# avt-trigger-shield.net
KiCad netlist of a schematic drawn in EAGLE
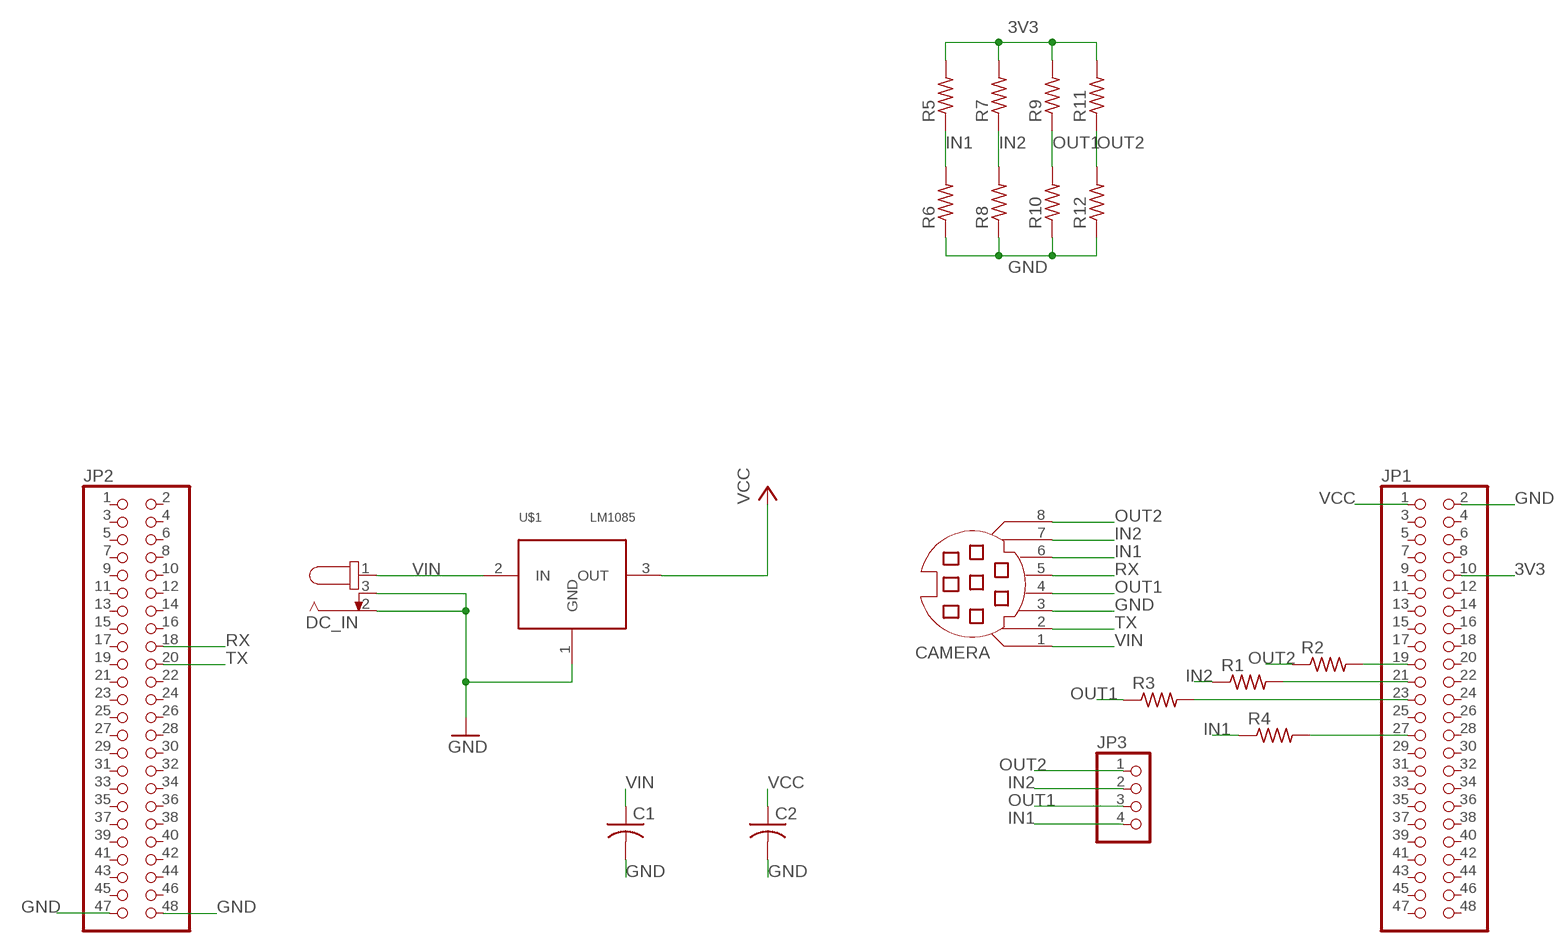
[diagram p0: schematic, sheet 1]

(export (version "E")
  (design (tool "Eeschema 10.0.6"))
  (components
    (comp (ref "C1")
      (value "C-USC1206")
      (footprint "eagle-import:C1206")
      (libsource (lib "eagle-import") (part "C-USC1206"))
    )
    (comp (ref "C2")
      (value "C-USC1206")
      (footprint "eagle-import:C1206")
      (libsource (lib "eagle-import") (part "C-USC1206"))
    )
    (comp (ref "CAMERA")
      (value "MD08SS")
      (footprint "eagle-import:MDIN08SS")
      (libsource (lib "eagle-import") (part "MD08SS"))
    )
    (comp (ref "DC_IN")
      (value "694106105102")
      (footprint "eagle-import:694106105102")
      (libsource (lib "eagle-import") (part "694106105102"))
    )
    (comp (ref "JP1")
      (value "PINHD-2X24")
      (footprint "eagle-import:2X24")
      (libsource (lib "eagle-import") (part "PINHD-2X24"))
    )
    (comp (ref "JP2")
      (value "PINHD-2X24")
      (footprint "eagle-import:2X24")
      (libsource (lib "eagle-import") (part "PINHD-2X24"))
    )
    (comp (ref "JP3")
      (value "PINHD-1X4")
      (footprint "eagle-import:1X04")
      (libsource (lib "eagle-import") (part "PINHD-1X4"))
    )
    (comp (ref "R1")
      (value "R-US_R0603")
      (footprint "eagle-import:R0603")
      (libsource (lib "eagle-import") (part "R-US_R0603"))
    )
    (comp (ref "R2")
      (value "R-US_R0603")
      (footprint "eagle-import:R0603")
      (libsource (lib "eagle-import") (part "R-US_R0603"))
    )
    (comp (ref "R3")
      (value "R-US_R0603")
      (footprint "eagle-import:R0603")
      (libsource (lib "eagle-import") (part "R-US_R0603"))
    )
    (comp (ref "R4")
      (value "R-US_R0603")
      (footprint "eagle-import:R0603")
      (libsource (lib "eagle-import") (part "R-US_R0603"))
    )
    (comp (ref "R5")
      (value "R-US_R0603")
      (footprint "eagle-import:R0603")
      (libsource (lib "eagle-import") (part "R-US_R0603"))
    )
    (comp (ref "R6")
      (value "R-US_R0603")
      (footprint "eagle-import:R0603")
      (libsource (lib "eagle-import") (part "R-US_R0603"))
    )
    (comp (ref "R7")
      (value "R-US_R0603")
      (footprint "eagle-import:R0603")
      (libsource (lib "eagle-import") (part "R-US_R0603"))
    )
    (comp (ref "R8")
      (value "R-US_R0603")
      (footprint "eagle-import:R0603")
      (libsource (lib "eagle-import") (part "R-US_R0603"))
    )
    (comp (ref "R9")
      (value "R-US_R0603")
      (footprint "eagle-import:R0603")
      (libsource (lib "eagle-import") (part "R-US_R0603"))
    )
    (comp (ref "R10")
      (value "R-US_R0603")
      (footprint "eagle-import:R0603")
      (libsource (lib "eagle-import") (part "R-US_R0603"))
    )
    (comp (ref "R11")
      (value "R-US_R0603")
      (footprint "eagle-import:R0603")
      (libsource (lib "eagle-import") (part "R-US_R0603"))
    )
    (comp (ref "R12")
      (value "R-US_R0603")
      (footprint "eagle-import:R0603")
      (libsource (lib "eagle-import") (part "R-US_R0603"))
    )
    (comp (ref "U$1")
      (value "LM1085")
      (footprint "eagle-import:TO263")
      (libsource (lib "eagle-import") (part "LM1085"))
    )
  )
  (nets
    (net (code "1") (name "/3V3") (class "Default")
      (node (ref "JP1") (pin "10") (pinfunction "10_10") (pintype "passive"))
      (node (ref "R11") (pin "2") (pinfunction "2_2") (pintype "passive"))
      (node (ref "R5") (pin "2") (pinfunction "2_2") (pintype "passive"))
      (node (ref "R7") (pin "2") (pinfunction "2_2") (pintype "passive"))
      (node (ref "R9") (pin "2") (pinfunction "2_2") (pintype "passive"))
    )
    (net (code "2") (name "/IN1") (class "Default")
      (node (ref "CAMERA") (pin "6") (pinfunction "6_6") (pintype "passive"))
      (node (ref "JP3") (pin "4") (pinfunction "4_4") (pintype "passive"))
      (node (ref "R4") (pin "1") (pinfunction "1_1") (pintype "passive"))
      (node (ref "R5") (pin "1") (pinfunction "1_1") (pintype "passive"))
      (node (ref "R6") (pin "2") (pinfunction "2_2") (pintype "passive"))
    )
    (net (code "3") (name "/IN2") (class "Default")
      (node (ref "CAMERA") (pin "7") (pinfunction "7_7") (pintype "passive"))
      (node (ref "JP3") (pin "2") (pinfunction "2_2") (pintype "passive"))
      (node (ref "R1") (pin "1") (pinfunction "1_1") (pintype "passive"))
      (node (ref "R7") (pin "1") (pinfunction "1_1") (pintype "passive"))
      (node (ref "R8") (pin "2") (pinfunction "2_2") (pintype "passive"))
    )
    (net (code "4") (name "/OUT1") (class "Default")
      (node (ref "CAMERA") (pin "4") (pinfunction "4_4") (pintype "passive"))
      (node (ref "JP3") (pin "3") (pinfunction "3_3") (pintype "passive"))
      (node (ref "R10") (pin "2") (pinfunction "2_2") (pintype "passive"))
      (node (ref "R3") (pin "1") (pinfunction "1_1") (pintype "passive"))
      (node (ref "R9") (pin "1") (pinfunction "1_1") (pintype "passive"))
    )
    (net (code "5") (name "/OUT2") (class "Default")
      (node (ref "CAMERA") (pin "8") (pinfunction "8_8") (pintype "passive"))
      (node (ref "JP3") (pin "1") (pinfunction "1_1") (pintype "passive"))
      (node (ref "R11") (pin "1") (pinfunction "1_1") (pintype "passive"))
      (node (ref "R12") (pin "2") (pinfunction "2_2") (pintype "passive"))
      (node (ref "R2") (pin "1") (pinfunction "1_1") (pintype "passive"))
    )
    (net (code "6") (name "/RX") (class "Default")
      (node (ref "CAMERA") (pin "5") (pinfunction "5_5") (pintype "passive"))
      (node (ref "JP2") (pin "18") (pinfunction "18_18") (pintype "passive"))
    )
    (net (code "7") (name "/TX") (class "Default")
      (node (ref "CAMERA") (pin "2") (pinfunction "2_2") (pintype "passive"))
      (node (ref "JP2") (pin "20") (pinfunction "20_20") (pintype "passive"))
    )
    (net (code "8") (name "/VIN") (class "Default")
      (node (ref "C1") (pin "1") (pinfunction "1_1") (pintype "passive"))
      (node (ref "CAMERA") (pin "1") (pinfunction "1_1") (pintype "passive"))
      (node (ref "DC_IN") (pin "1") (pinfunction "1_1") (pintype "passive"))
      (node (ref "U$1") (pin "2") (pinfunction "IN_2") (pintype "bidirectional"))
    )
    (net (code "9") (name "GND") (class "Default")
      (node (ref "C1") (pin "2") (pinfunction "2_2") (pintype "passive"))
      (node (ref "C2") (pin "2") (pinfunction "2_2") (pintype "passive"))
      (node (ref "CAMERA") (pin "3") (pinfunction "3_3") (pintype "passive"))
      (node (ref "DC_IN") (pin "2") (pinfunction "2_2") (pintype "passive"))
      (node (ref "DC_IN") (pin "3") (pinfunction "3_3") (pintype "passive"))
      (node (ref "JP1") (pin "2") (pinfunction "2_2") (pintype "passive"))
      (node (ref "JP2") (pin "47") (pinfunction "47_47") (pintype "passive"))
      (node (ref "JP2") (pin "48") (pinfunction "48_48") (pintype "passive"))
      (node (ref "R10") (pin "1") (pinfunction "1_1") (pintype "passive"))
      (node (ref "R12") (pin "1") (pinfunction "1_1") (pintype "passive"))
      (node (ref "R6") (pin "1") (pinfunction "1_1") (pintype "passive"))
      (node (ref "R8") (pin "1") (pinfunction "1_1") (pintype "passive"))
      (node (ref "U$1") (pin "1") (pinfunction "GND_1") (pintype "bidirectional"))
    )
    (net (code "10") (name "Net-(JP1-Pad19)") (class "Default")
      (node (ref "JP1") (pin "19") (pinfunction "19_19") (pintype "passive"))
      (node (ref "R2") (pin "2") (pinfunction "2_2") (pintype "passive"))
    )
    (net (code "11") (name "Net-(JP1-Pad21)") (class "Default")
      (node (ref "JP1") (pin "21") (pinfunction "21_21") (pintype "passive"))
      (node (ref "R1") (pin "2") (pinfunction "2_2") (pintype "passive"))
    )
    (net (code "12") (name "Net-(JP1-Pad23)") (class "Default")
      (node (ref "JP1") (pin "23") (pinfunction "23_23") (pintype "passive"))
      (node (ref "R3") (pin "2") (pinfunction "2_2") (pintype "passive"))
    )
    (net (code "13") (name "Net-(JP1-Pad27)") (class "Default")
      (node (ref "JP1") (pin "27") (pinfunction "27_27") (pintype "passive"))
      (node (ref "R4") (pin "2") (pinfunction "2_2") (pintype "passive"))
    )
    (net (code "14") (name "VCC") (class "Default")
      (node (ref "C2") (pin "1") (pinfunction "1_1") (pintype "passive"))
      (node (ref "JP1") (pin "1") (pinfunction "1_1") (pintype "passive"))
      (node (ref "U$1") (pin "3") (pinfunction "OUT_3") (pintype "bidirectional"))
    )
    (net (code "15") (name "unconnected-(JP1-Pad3)") (class "Default")
      (node (ref "JP1") (pin "3") (pinfunction "3_3") (pintype "passive"))
    )
    (net (code "16") (name "unconnected-(JP1-Pad4)") (class "Default")
      (node (ref "JP1") (pin "4") (pinfunction "4_4") (pintype "passive"))
    )
    (net (code "17") (name "unconnected-(JP1-Pad5)") (class "Default")
      (node (ref "JP1") (pin "5") (pinfunction "5_5") (pintype "passive"))
    )
    (net (code "18") (name "unconnected-(JP1-Pad6)") (class "Default")
      (node (ref "JP1") (pin "6") (pinfunction "6_6") (pintype "passive"))
    )
    (net (code "19") (name "unconnected-(JP1-Pad7)") (class "Default")
      (node (ref "JP1") (pin "7") (pinfunction "7_7") (pintype "passive"))
    )
    (net (code "20") (name "unconnected-(JP1-Pad8)") (class "Default")
      (node (ref "JP1") (pin "8") (pinfunction "8_8") (pintype "passive"))
    )
    (net (code "21") (name "unconnected-(JP1-Pad9)") (class "Default")
      (node (ref "JP1") (pin "9") (pinfunction "9_9") (pintype "passive"))
    )
    (net (code "22") (name "unconnected-(JP1-Pad11)") (class "Default")
      (node (ref "JP1") (pin "11") (pinfunction "11_11") (pintype "passive"))
    )
    (net (code "23") (name "unconnected-(JP1-Pad12)") (class "Default")
      (node (ref "JP1") (pin "12") (pinfunction "12_12") (pintype "passive"))
    )
    (net (code "24") (name "unconnected-(JP1-Pad13)") (class "Default")
      (node (ref "JP1") (pin "13") (pinfunction "13_13") (pintype "passive"))
    )
    (net (code "25") (name "unconnected-(JP1-Pad14)") (class "Default")
      (node (ref "JP1") (pin "14") (pinfunction "14_14") (pintype "passive"))
    )
    (net (code "26") (name "unconnected-(JP1-Pad15)") (class "Default")
      (node (ref "JP1") (pin "15") (pinfunction "15_15") (pintype "passive"))
    )
    (net (code "27") (name "unconnected-(JP1-Pad16)") (class "Default")
      (node (ref "JP1") (pin "16") (pinfunction "16_16") (pintype "passive"))
    )
    (net (code "28") (name "unconnected-(JP1-Pad17)") (class "Default")
      (node (ref "JP1") (pin "17") (pinfunction "17_17") (pintype "passive"))
    )
    (net (code "29") (name "unconnected-(JP1-Pad18)") (class "Default")
      (node (ref "JP1") (pin "18") (pinfunction "18_18") (pintype "passive"))
    )
    (net (code "30") (name "unconnected-(JP1-Pad20)") (class "Default")
      (node (ref "JP1") (pin "20") (pinfunction "20_20") (pintype "passive"))
    )
    (net (code "31") (name "unconnected-(JP1-Pad22)") (class "Default")
      (node (ref "JP1") (pin "22") (pinfunction "22_22") (pintype "passive"))
    )
    (net (code "32") (name "unconnected-(JP1-Pad24)") (class "Default")
      (node (ref "JP1") (pin "24") (pinfunction "24_24") (pintype "passive"))
    )
    (net (code "33") (name "unconnected-(JP1-Pad25)") (class "Default")
      (node (ref "JP1") (pin "25") (pinfunction "25_25") (pintype "passive"))
    )
    (net (code "34") (name "unconnected-(JP1-Pad26)") (class "Default")
      (node (ref "JP1") (pin "26") (pinfunction "26_26") (pintype "passive"))
    )
    (net (code "35") (name "unconnected-(JP1-Pad28)") (class "Default")
      (node (ref "JP1") (pin "28") (pinfunction "28_28") (pintype "passive"))
    )
    (net (code "36") (name "unconnected-(JP1-Pad29)") (class "Default")
      (node (ref "JP1") (pin "29") (pinfunction "29_29") (pintype "passive"))
    )
    (net (code "37") (name "unconnected-(JP1-Pad30)") (class "Default")
      (node (ref "JP1") (pin "30") (pinfunction "30_30") (pintype "passive"))
    )
    (net (code "38") (name "unconnected-(JP1-Pad31)") (class "Default")
      (node (ref "JP1") (pin "31") (pinfunction "31_31") (pintype "passive"))
    )
    (net (code "39") (name "unconnected-(JP1-Pad32)") (class "Default")
      (node (ref "JP1") (pin "32") (pinfunction "32_32") (pintype "passive"))
    )
    (net (code "40") (name "unconnected-(JP1-Pad33)") (class "Default")
      (node (ref "JP1") (pin "33") (pinfunction "33_33") (pintype "passive"))
    )
    (net (code "41") (name "unconnected-(JP1-Pad34)") (class "Default")
      (node (ref "JP1") (pin "34") (pinfunction "34_34") (pintype "passive"))
    )
    (net (code "42") (name "unconnected-(JP1-Pad35)") (class "Default")
      (node (ref "JP1") (pin "35") (pinfunction "35_35") (pintype "passive"))
    )
    (net (code "43") (name "unconnected-(JP1-Pad36)") (class "Default")
      (node (ref "JP1") (pin "36") (pinfunction "36_36") (pintype "passive"))
    )
    (net (code "44") (name "unconnected-(JP1-Pad37)") (class "Default")
      (node (ref "JP1") (pin "37") (pinfunction "37_37") (pintype "passive"))
    )
    (net (code "45") (name "unconnected-(JP1-Pad38)") (class "Default")
      (node (ref "JP1") (pin "38") (pinfunction "38_38") (pintype "passive"))
    )
    (net (code "46") (name "unconnected-(JP1-Pad39)") (class "Default")
      (node (ref "JP1") (pin "39") (pinfunction "39_39") (pintype "passive"))
    )
    (net (code "47") (name "unconnected-(JP1-Pad40)") (class "Default")
      (node (ref "JP1") (pin "40") (pinfunction "40_40") (pintype "passive"))
    )
    (net (code "48") (name "unconnected-(JP1-Pad41)") (class "Default")
      (node (ref "JP1") (pin "41") (pinfunction "41_41") (pintype "passive"))
    )
    (net (code "49") (name "unconnected-(JP1-Pad42)") (class "Default")
      (node (ref "JP1") (pin "42") (pinfunction "42_42") (pintype "passive"))
    )
    (net (code "50") (name "unconnected-(JP1-Pad43)") (class "Default")
      (node (ref "JP1") (pin "43") (pinfunction "43_43") (pintype "passive"))
    )
    (net (code "51") (name "unconnected-(JP1-Pad44)") (class "Default")
      (node (ref "JP1") (pin "44") (pinfunction "44_44") (pintype "passive"))
    )
    (net (code "52") (name "unconnected-(JP1-Pad45)") (class "Default")
      (node (ref "JP1") (pin "45") (pinfunction "45_45") (pintype "passive"))
    )
    (net (code "53") (name "unconnected-(JP1-Pad46)") (class "Default")
      (node (ref "JP1") (pin "46") (pinfunction "46_46") (pintype "passive"))
    )
    (net (code "54") (name "unconnected-(JP1-Pad47)") (class "Default")
      (node (ref "JP1") (pin "47") (pinfunction "47_47") (pintype "passive"))
    )
    (net (code "55") (name "unconnected-(JP1-Pad48)") (class "Default")
      (node (ref "JP1") (pin "48") (pinfunction "48_48") (pintype "passive"))
    )
    (net (code "56") (name "unconnected-(JP2-Pad1)") (class "Default")
      (node (ref "JP2") (pin "1") (pinfunction "1_1") (pintype "passive"))
    )
    (net (code "57") (name "unconnected-(JP2-Pad2)") (class "Default")
      (node (ref "JP2") (pin "2") (pinfunction "2_2") (pintype "passive"))
    )
    (net (code "58") (name "unconnected-(JP2-Pad3)") (class "Default")
      (node (ref "JP2") (pin "3") (pinfunction "3_3") (pintype "passive"))
    )
    (net (code "59") (name "unconnected-(JP2-Pad4)") (class "Default")
      (node (ref "JP2") (pin "4") (pinfunction "4_4") (pintype "passive"))
    )
    (net (code "60") (name "unconnected-(JP2-Pad5)") (class "Default")
      (node (ref "JP2") (pin "5") (pinfunction "5_5") (pintype "passive"))
    )
    (net (code "61") (name "unconnected-(JP2-Pad6)") (class "Default")
      (node (ref "JP2") (pin "6") (pinfunction "6_6") (pintype "passive"))
    )
    (net (code "62") (name "unconnected-(JP2-Pad7)") (class "Default")
      (node (ref "JP2") (pin "7") (pinfunction "7_7") (pintype "passive"))
    )
    (net (code "63") (name "unconnected-(JP2-Pad8)") (class "Default")
      (node (ref "JP2") (pin "8") (pinfunction "8_8") (pintype "passive"))
    )
    (net (code "64") (name "unconnected-(JP2-Pad9)") (class "Default")
      (node (ref "JP2") (pin "9") (pinfunction "9_9") (pintype "passive"))
    )
    (net (code "65") (name "unconnected-(JP2-Pad10)") (class "Default")
      (node (ref "JP2") (pin "10") (pinfunction "10_10") (pintype "passive"))
    )
    (net (code "66") (name "unconnected-(JP2-Pad11)") (class "Default")
      (node (ref "JP2") (pin "11") (pinfunction "11_11") (pintype "passive"))
    )
    (net (code "67") (name "unconnected-(JP2-Pad12)") (class "Default")
      (node (ref "JP2") (pin "12") (pinfunction "12_12") (pintype "passive"))
    )
    (net (code "68") (name "unconnected-(JP2-Pad13)") (class "Default")
      (node (ref "JP2") (pin "13") (pinfunction "13_13") (pintype "passive"))
    )
    (net (code "69") (name "unconnected-(JP2-Pad14)") (class "Default")
      (node (ref "JP2") (pin "14") (pinfunction "14_14") (pintype "passive"))
    )
    (net (code "70") (name "unconnected-(JP2-Pad15)") (class "Default")
      (node (ref "JP2") (pin "15") (pinfunction "15_15") (pintype "passive"))
    )
    (net (code "71") (name "unconnected-(JP2-Pad16)") (class "Default")
      (node (ref "JP2") (pin "16") (pinfunction "16_16") (pintype "passive"))
    )
    (net (code "72") (name "unconnected-(JP2-Pad17)") (class "Default")
      (node (ref "JP2") (pin "17") (pinfunction "17_17") (pintype "passive"))
    )
    (net (code "73") (name "unconnected-(JP2-Pad19)") (class "Default")
      (node (ref "JP2") (pin "19") (pinfunction "19_19") (pintype "passive"))
    )
    (net (code "74") (name "unconnected-(JP2-Pad21)") (class "Default")
      (node (ref "JP2") (pin "21") (pinfunction "21_21") (pintype "passive"))
    )
    (net (code "75") (name "unconnected-(JP2-Pad22)") (class "Default")
      (node (ref "JP2") (pin "22") (pinfunction "22_22") (pintype "passive"))
    )
    (net (code "76") (name "unconnected-(JP2-Pad23)") (class "Default")
      (node (ref "JP2") (pin "23") (pinfunction "23_23") (pintype "passive"))
    )
    (net (code "77") (name "unconnected-(JP2-Pad24)") (class "Default")
      (node (ref "JP2") (pin "24") (pinfunction "24_24") (pintype "passive"))
    )
    (net (code "78") (name "unconnected-(JP2-Pad25)") (class "Default")
      (node (ref "JP2") (pin "25") (pinfunction "25_25") (pintype "passive"))
    )
    (net (code "79") (name "unconnected-(JP2-Pad26)") (class "Default")
      (node (ref "JP2") (pin "26") (pinfunction "26_26") (pintype "passive"))
    )
    (net (code "80") (name "unconnected-(JP2-Pad27)") (class "Default")
      (node (ref "JP2") (pin "27") (pinfunction "27_27") (pintype "passive"))
    )
    (net (code "81") (name "unconnected-(JP2-Pad28)") (class "Default")
      (node (ref "JP2") (pin "28") (pinfunction "28_28") (pintype "passive"))
    )
    (net (code "82") (name "unconnected-(JP2-Pad29)") (class "Default")
      (node (ref "JP2") (pin "29") (pinfunction "29_29") (pintype "passive"))
    )
    (net (code "83") (name "unconnected-(JP2-Pad30)") (class "Default")
      (node (ref "JP2") (pin "30") (pinfunction "30_30") (pintype "passive"))
    )
    (net (code "84") (name "unconnected-(JP2-Pad31)") (class "Default")
      (node (ref "JP2") (pin "31") (pinfunction "31_31") (pintype "passive"))
    )
    (net (code "85") (name "unconnected-(JP2-Pad32)") (class "Default")
      (node (ref "JP2") (pin "32") (pinfunction "32_32") (pintype "passive"))
    )
    (net (code "86") (name "unconnected-(JP2-Pad33)") (class "Default")
      (node (ref "JP2") (pin "33") (pinfunction "33_33") (pintype "passive"))
    )
    (net (code "87") (name "unconnected-(JP2-Pad34)") (class "Default")
      (node (ref "JP2") (pin "34") (pinfunction "34_34") (pintype "passive"))
    )
    (net (code "88") (name "unconnected-(JP2-Pad35)") (class "Default")
      (node (ref "JP2") (pin "35") (pinfunction "35_35") (pintype "passive"))
    )
    (net (code "89") (name "unconnected-(JP2-Pad36)") (class "Default")
      (node (ref "JP2") (pin "36") (pinfunction "36_36") (pintype "passive"))
    )
    (net (code "90") (name "unconnected-(JP2-Pad37)") (class "Default")
      (node (ref "JP2") (pin "37") (pinfunction "37_37") (pintype "passive"))
    )
    (net (code "91") (name "unconnected-(JP2-Pad38)") (class "Default")
      (node (ref "JP2") (pin "38") (pinfunction "38_38") (pintype "passive"))
    )
    (net (code "92") (name "unconnected-(JP2-Pad39)") (class "Default")
      (node (ref "JP2") (pin "39") (pinfunction "39_39") (pintype "passive"))
    )
    (net (code "93") (name "unconnected-(JP2-Pad40)") (class "Default")
      (node (ref "JP2") (pin "40") (pinfunction "40_40") (pintype "passive"))
    )
    (net (code "94") (name "unconnected-(JP2-Pad41)") (class "Default")
      (node (ref "JP2") (pin "41") (pinfunction "41_41") (pintype "passive"))
    )
    (net (code "95") (name "unconnected-(JP2-Pad42)") (class "Default")
      (node (ref "JP2") (pin "42") (pinfunction "42_42") (pintype "passive"))
    )
    (net (code "96") (name "unconnected-(JP2-Pad43)") (class "Default")
      (node (ref "JP2") (pin "43") (pinfunction "43_43") (pintype "passive"))
    )
    (net (code "97") (name "unconnected-(JP2-Pad44)") (class "Default")
      (node (ref "JP2") (pin "44") (pinfunction "44_44") (pintype "passive"))
    )
    (net (code "98") (name "unconnected-(JP2-Pad45)") (class "Default")
      (node (ref "JP2") (pin "45") (pinfunction "45_45") (pintype "passive"))
    )
    (net (code "99") (name "unconnected-(JP2-Pad46)") (class "Default")
      (node (ref "JP2") (pin "46") (pinfunction "46_46") (pintype "passive"))
    )
  )
)
